# TEC_driver.net
KiCad netlist of a schematic drawn in Altium Designer
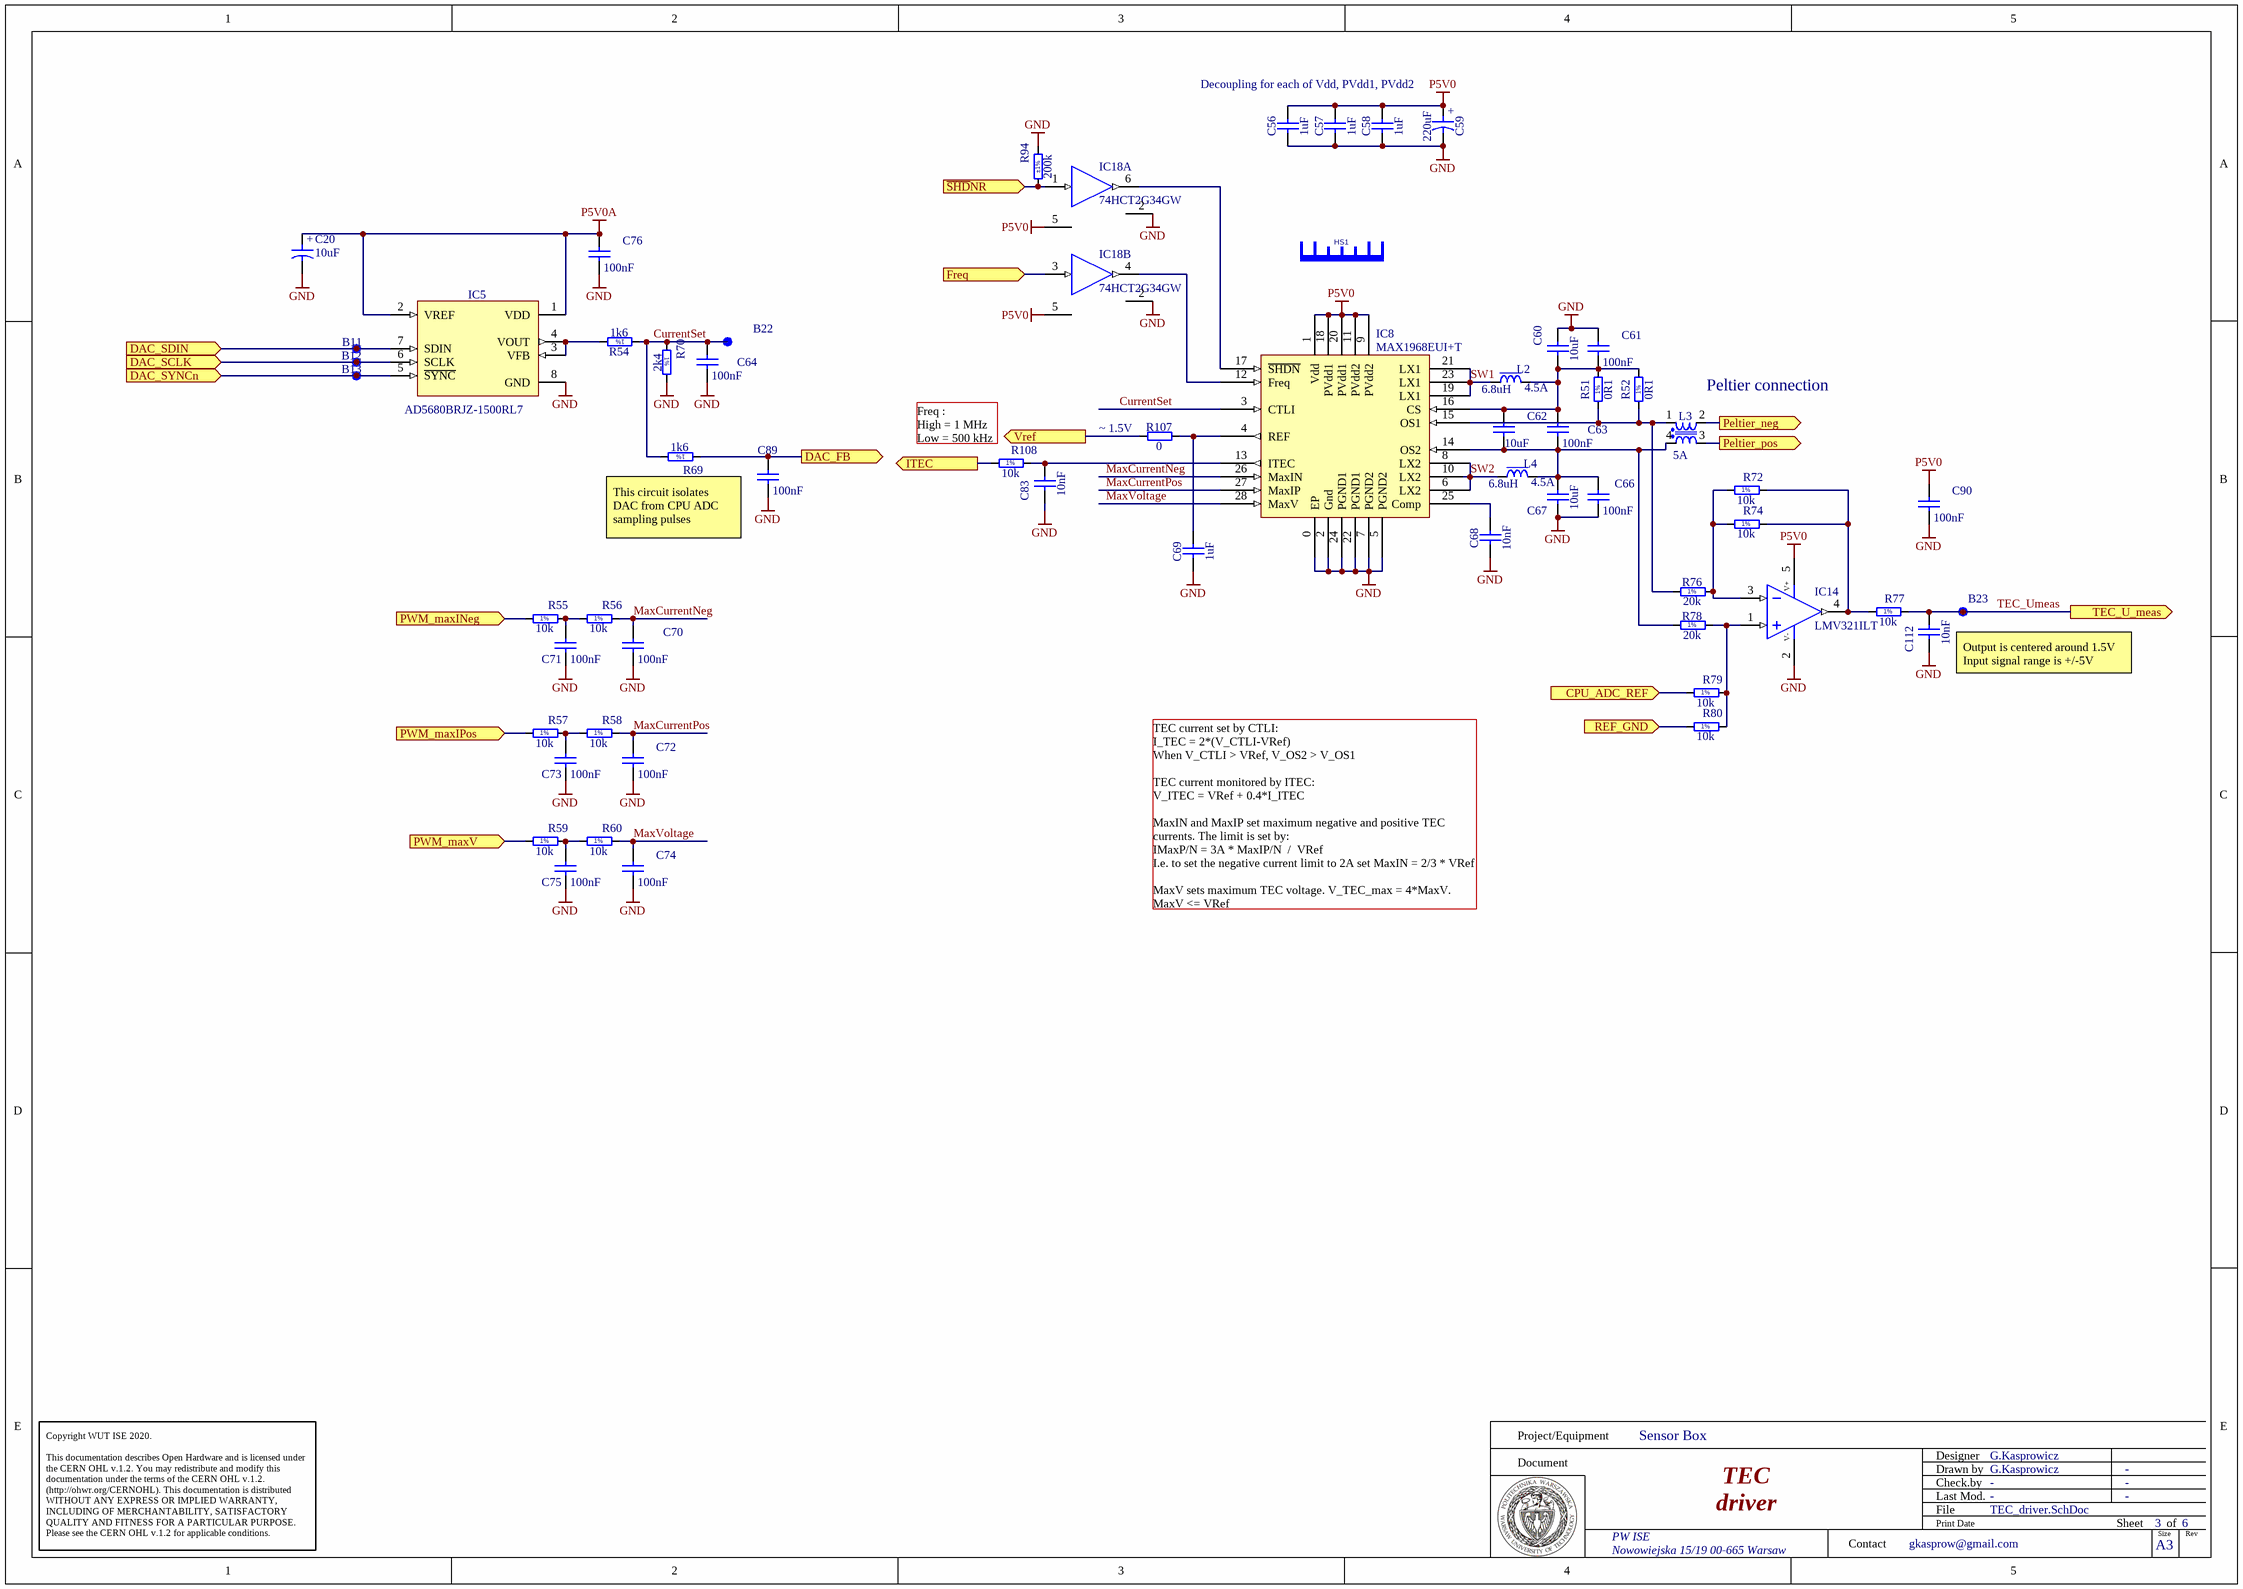
[diagram p0: TEC_driver.SchDoc]

(export (version "E")
  (design (tool "Eeschema 10.0.6"))
  (components
    (comp (ref "B11")
      (value "SMD Pad")
      (footprint "C100")
      (description "Through Hole Pad")
      (fields (field (name "PART NUMBER") "SMD_PAD_D1MM") (field (name "AUTHOR") "CERN DEM JLC"))
      (libsource (lib "Eletro-mechanical") (part "Single SMD Pad (Round)"))
    )
    (comp (ref "B12")
      (value "SMD Pad")
      (footprint "C100")
      (description "Through Hole Pad")
      (fields (field (name "PART NUMBER") "SMD_PAD_D1MM") (field (name "AUTHOR") "CERN DEM JLC"))
      (libsource (lib "Eletro-mechanical") (part "Single SMD Pad (Round)"))
    )
    (comp (ref "B13")
      (value "SMD Pad")
      (footprint "C100")
      (description "Through Hole Pad")
      (fields (field (name "PART NUMBER") "SMD_PAD_D1MM") (field (name "AUTHOR") "CERN DEM JLC"))
      (libsource (lib "Eletro-mechanical") (part "Single SMD Pad (Round)"))
    )
    (comp (ref "B22")
      (value "SMD Pad")
      (footprint "C100")
      (description "Through Hole Pad")
      (fields (field (name "PART NUMBER") "SMD_PAD_D1MM") (field (name "AUTHOR") "CERN DEM JLC"))
      (libsource (lib "Eletro-mechanical") (part "Single SMD Pad (Round)"))
    )
    (comp (ref "B23")
      (value "SMD Pad")
      (footprint "C100")
      (description "Through Hole Pad")
      (fields (field (name "PART NUMBER") "SMD_PAD_D1MM") (field (name "AUTHOR") "CERN DEM JLC"))
      (libsource (lib "Eletro-mechanical") (part "Single SMD Pad (Round)"))
    )
    (comp (ref "C20")
      (value "10uF")
      (footprint "CAPMP3216X180N")
      (description "Polarised capacitor")
      (fields
        (field (name "PART NUMBER") "CTE3216-18_10UF_16V_20%_AVX_TCJ")
        (field (name "VOLTAGE") "16V")
        (field (name "AUTHOR") "CERN DEM JLC")
      )
      (libsource (lib "Capacitors") (part "Capacitor - polarized"))
    )
    (comp (ref "C56")
      (value "1uF")
      (footprint "CAPC1608X87N")
      (description "Non-polarised capacitor")
      (fields
        (field (name "PART NUMBER") "CC0603_1UF_25V_10%_X7R")
        (field (name "VOLTAGE") "25V")
        (field (name "AUTHOR") "CERN DEM JLC")
      )
      (libsource (lib "Capacitors") (part "Capacitor - non polarized"))
    )
    (comp (ref "C57")
      (value "1uF")
      (footprint "CAPC1608X87N")
      (description "Non-polarised capacitor")
      (fields
        (field (name "PART NUMBER") "CC0603_1UF_25V_10%_X7R")
        (field (name "VOLTAGE") "25V")
        (field (name "AUTHOR") "CERN DEM JLC")
      )
      (libsource (lib "Capacitors") (part "Capacitor - non polarized"))
    )
    (comp (ref "C58")
      (value "1uF")
      (footprint "CAPC1608X87N")
      (description "Non-polarised capacitor")
      (fields
        (field (name "PART NUMBER") "CC0603_1UF_25V_10%_X7R")
        (field (name "VOLTAGE") "25V")
        (field (name "AUTHOR") "CERN DEM JLC")
      )
      (libsource (lib "Capacitors") (part "Capacitor - non polarized"))
    )
    (comp (ref "C59")
      (value "220uF")
      (footprint "CAPMP7343X430N")
      (description "Polarised capacitor")
      (fields
        (field (name "PART NUMBER") "CTE7343-43_220UF_16V_10%")
        (field (name "VOLTAGE") "16V")
        (field (name "AUTHOR") "CERN DEM JLC")
      )
      (libsource (lib "Capacitors") (part "Capacitor - polarized"))
    )
    (comp (ref "C60")
      (value "10uF")
      (footprint "CAPC2012X135N")
      (description "Non-polarised capacitor")
      (fields
        (field (name "PART NUMBER") "CC0805_10UF_16V_10%_X5R")
        (field (name "VOLTAGE") "16V")
        (field (name "AUTHOR") "CERN DEM JLC")
      )
      (libsource (lib "Capacitors") (part "Capacitor - non polarized"))
    )
    (comp (ref "C61")
      (value "100nF")
      (footprint "CAPC1005X55N")
      (description "Non-polarised capacitor")
      (fields
        (field (name "PART NUMBER") "CC0402_100NF_16V_10%_X5R")
        (field (name "VOLTAGE") "16V")
        (field (name "AUTHOR") "CERN DEM JLC")
      )
      (libsource (lib "Capacitors") (part "Capacitor - non polarized"))
    )
    (comp (ref "C62")
      (value "10uF")
      (footprint "CAPC2012X135N")
      (description "Non-polarised capacitor")
      (fields
        (field (name "PART NUMBER") "CC0805_10UF_16V_10%_X5R")
        (field (name "VOLTAGE") "16V")
        (field (name "AUTHOR") "CERN DEM JLC")
      )
      (libsource (lib "Capacitors") (part "Capacitor - non polarized"))
    )
    (comp (ref "C63")
      (value "100nF")
      (footprint "CAPC1005X55N")
      (description "Non-polarised capacitor")
      (fields
        (field (name "PART NUMBER") "CC0402_100NF_16V_10%_X5R")
        (field (name "VOLTAGE") "16V")
        (field (name "AUTHOR") "CERN DEM JLC")
      )
      (libsource (lib "Capacitors") (part "Capacitor - non polarized"))
    )
    (comp (ref "C64")
      (value "100nF")
      (footprint "CAPC1005X55N")
      (description "Non-polarised capacitor")
      (fields
        (field (name "PART NUMBER") "CC0402_100NF_16V_10%_X5R")
        (field (name "VOLTAGE") "16V")
        (field (name "AUTHOR") "CERN DEM JLC")
      )
      (libsource (lib "Capacitors") (part "Capacitor - non polarized"))
    )
    (comp (ref "C66")
      (value "100nF")
      (footprint "CAPC1005X55N")
      (description "Non-polarised capacitor")
      (fields
        (field (name "PART NUMBER") "CC0402_100NF_16V_10%_X5R")
        (field (name "VOLTAGE") "16V")
        (field (name "AUTHOR") "CERN DEM JLC")
      )
      (libsource (lib "Capacitors") (part "Capacitor - non polarized"))
    )
    (comp (ref "C67")
      (value "10uF")
      (footprint "CAPC2012X135N")
      (description "Non-polarised capacitor")
      (fields
        (field (name "PART NUMBER") "CC0805_10UF_16V_10%_X5R")
        (field (name "VOLTAGE") "16V")
        (field (name "AUTHOR") "CERN DEM JLC")
      )
      (libsource (lib "Capacitors") (part "Capacitor - non polarized"))
    )
    (comp (ref "C68")
      (value "10nF")
      (footprint "CAPC1005X55N")
      (description "Non-polarised capacitor")
      (fields
        (field (name "PART NUMBER") "CC0402_10NF_50V_10%_X7R")
        (field (name "VOLTAGE") "50V")
        (field (name "AUTHOR") "CERN DEM MR")
      )
      (libsource (lib "Capacitors") (part "Capacitor - non polarized"))
    )
    (comp (ref "C69")
      (value "1uF")
      (footprint "CAPC1608X87N")
      (description "Non-polarised capacitor")
      (fields
        (field (name "PART NUMBER") "CC0603_1UF_25V_10%_X7R")
        (field (name "VOLTAGE") "25V")
        (field (name "AUTHOR") "CERN DEM JLC")
      )
      (libsource (lib "Capacitors") (part "Capacitor - non polarized"))
    )
    (comp (ref "C70")
      (value "100nF")
      (footprint "CAPC1005X55N")
      (description "Non-polarised capacitor")
      (fields
        (field (name "PART NUMBER") "CC0402_100NF_16V_10%_X5R")
        (field (name "VOLTAGE") "16V")
        (field (name "AUTHOR") "CERN DEM JLC")
      )
      (libsource (lib "Capacitors") (part "Capacitor - non polarized"))
    )
    (comp (ref "C71")
      (value "100nF")
      (footprint "CAPC1005X55N")
      (description "Non-polarised capacitor")
      (fields
        (field (name "PART NUMBER") "CC0402_100NF_16V_10%_X5R")
        (field (name "VOLTAGE") "16V")
        (field (name "AUTHOR") "CERN DEM JLC")
      )
      (libsource (lib "Capacitors") (part "Capacitor - non polarized"))
    )
    (comp (ref "C72")
      (value "100nF")
      (footprint "CAPC1005X55N")
      (description "Non-polarised capacitor")
      (fields
        (field (name "PART NUMBER") "CC0402_100NF_16V_10%_X5R")
        (field (name "VOLTAGE") "16V")
        (field (name "AUTHOR") "CERN DEM JLC")
      )
      (libsource (lib "Capacitors") (part "Capacitor - non polarized"))
    )
    (comp (ref "C73")
      (value "100nF")
      (footprint "CAPC1005X55N")
      (description "Non-polarised capacitor")
      (fields
        (field (name "PART NUMBER") "CC0402_100NF_16V_10%_X5R")
        (field (name "VOLTAGE") "16V")
        (field (name "AUTHOR") "CERN DEM JLC")
      )
      (libsource (lib "Capacitors") (part "Capacitor - non polarized"))
    )
    (comp (ref "C74")
      (value "100nF")
      (footprint "CAPC1005X55N")
      (description "Non-polarised capacitor")
      (fields
        (field (name "PART NUMBER") "CC0402_100NF_16V_10%_X5R")
        (field (name "VOLTAGE") "16V")
        (field (name "AUTHOR") "CERN DEM JLC")
      )
      (libsource (lib "Capacitors") (part "Capacitor - non polarized"))
    )
    (comp (ref "C75")
      (value "100nF")
      (footprint "CAPC1005X55N")
      (description "Non-polarised capacitor")
      (fields
        (field (name "PART NUMBER") "CC0402_100NF_16V_10%_X5R")
        (field (name "VOLTAGE") "16V")
        (field (name "AUTHOR") "CERN DEM JLC")
      )
      (libsource (lib "Capacitors") (part "Capacitor - non polarized"))
    )
    (comp (ref "C76")
      (value "100nF")
      (footprint "CAPC1005X55N")
      (description "Non-polarised capacitor")
      (fields
        (field (name "PART NUMBER") "CC0402_100NF_16V_10%_X5R")
        (field (name "VOLTAGE") "16V")
        (field (name "AUTHOR") "CERN DEM JLC")
      )
      (libsource (lib "Capacitors") (part "Capacitor - non polarized"))
    )
    (comp (ref "C83")
      (value "10nF")
      (footprint "CAPC1005X55N")
      (description "Non-polarised capacitor")
      (fields
        (field (name "PART NUMBER") "CC0402_10NF_25V_10%_X7R")
        (field (name "VOLTAGE") "25V")
        (field (name "AUTHOR") "CERN DEM JLC")
      )
      (libsource (lib "Capacitors") (part "Capacitor - non polarized"))
    )
    (comp (ref "C89")
      (value "100nF")
      (footprint "CAPC1005X55N")
      (description "Non-polarised capacitor")
      (fields
        (field (name "PART NUMBER") "CC0402_100NF_16V_10%_X5R")
        (field (name "VOLTAGE") "16V")
        (field (name "AUTHOR") "CERN DEM JLC")
      )
      (libsource (lib "Capacitors") (part "Capacitor - non polarized"))
    )
    (comp (ref "C90")
      (value "100nF")
      (footprint "CAPC1005X55N")
      (description "Non-polarised capacitor")
      (fields
        (field (name "PART NUMBER") "CC0402_100NF_16V_10%_X5R")
        (field (name "VOLTAGE") "16V")
        (field (name "AUTHOR") "CERN DEM JLC")
      )
      (libsource (lib "Capacitors") (part "Capacitor - non polarized"))
    )
    (comp (ref "C112")
      (value "10nF")
      (footprint "CAPC1005X55N")
      (description "Non-polarised capacitor")
      (fields
        (field (name "PART NUMBER") "CC0402_10NF_25V_10%_X7R")
        (field (name "VOLTAGE") "25V")
        (field (name "AUTHOR") "CERN DEM JLC")
      )
      (libsource (lib "Capacitors") (part "Capacitor - non polarized"))
    )
    (comp (ref "HS1")
      (value "Heat Sink No Pad")
      (footprint "HSINK_FISCHER_ICK_BGA_11x11x10")
      (description "Rth: 27.5K/W - L 11mm x W 11mm x H 10mm Black Anodized Heatsinks for BGA")
      (fields
        (field (name "PART NUMBER") "HSINK_FISCHER_ICK BGA 11 x 11 x 10")
        (field (name "MANUFACTURER") "FISCHER ELEKTRONIK")
        (field (name "AUTHOR") "GK")
      )
      (libsource (lib "Mechanical") (part "HEAT_SINK_BGA_11x11x10"))
    )
    (comp (ref "IC5")
      (value "AD5680BRJZ-1500RL7")
      (footprint "SOT65P280X145-8N")
      (description "5V 18-Bit nanoDAC®in a SOT-23")
      (fields (field (name "MANUFACTURER") "ANALOG DEVICES") (field (name "AUTHOR") "GK"))
      (libsource (lib "LIBRARY_SCH") (part "DAC_AD5680BRJZ"))
    )
    (comp (ref "IC8")
      (value "MAX1968EUI+T")
      (footprint "TSSOP28-EP")
      (description "Power peltier driver. bipolar")
      (fields (field (name "PUBLISHER") "Altium Limited"))
      (libsource (lib "LIBRARY_SCH") (part "DRV_MAX1968"))
    )
    (comp (ref "IC14")
      (value "LMV321ILT")
      (footprint "SOT95P280X145-5N")
      (description "Operational Amplifier")
      (fields (field (name "MANUFACTURER") "ST MICROELECTRONICS") (field (name "AUTHOR") "CERN DEM MR"))
      (libsource (lib "ICs And Semiconductors") (part "Operational Amplifier Type10"))
    )
    (comp (ref "IC18")
      (value "74HCT2G34GW")
      (footprint "SOT65P210X110-6N")
      (description "Dual Buffer Gate")
      (fields (field (name "MANUFACTURER") "TEXAS INSTRUMENTS") (field (name "AUTHOR") "GK"))
      (libsource (lib "ICS-logic") (part "74HCT2G34GW"))
    )
    (comp (ref "L2")
      (value "6.8uH")
      (footprint "INDM6965X300N")
      (description "Inductor With Core")
      (fields
        (field (name "PART NUMBER") "IND2525_6.8UH_20%_VISHAY_IHLP-2525CZ-01")
        (field (name "POWER") "4.5A")
        (field (name "TOLERANCE") "±20%")
        (field (name "AUTHOR") "CERN DEM MR")
      )
      (libsource (lib "Inductors & Transformers") (part "Inductor With Magnetic core"))
    )
    (comp (ref "L3")
      (value "600nH")
      (footprint "IND_BOURNS_SRF0504-191Y")
      (description "Inductor Common Mode")
      (fields
        (field (name "PART NUMBER") "IND_600NH_30%_BOURNS_SRF0504")
        (field (name "POWER") "5A")
        (field (name "TOLERANCE") "±30%")
        (field (name "AUTHOR") "CERN DEM MR")
      )
      (libsource (lib "Inductors & Transformers") (part "Inductor Common Mode 1Dot-2 4Dot-3"))
    )
    (comp (ref "L4")
      (value "6.8uH")
      (footprint "INDM6965X300N")
      (description "Inductor With Core")
      (fields
        (field (name "PART NUMBER") "IND2525_6.8UH_20%_VISHAY_IHLP-2525CZ-01")
        (field (name "POWER") "4.5A")
        (field (name "TOLERANCE") "±20%")
        (field (name "AUTHOR") "CERN DEM MR")
      )
      (libsource (lib "Inductors & Transformers") (part "Inductor With Magnetic core"))
    )
    (comp (ref "R51")
      (value "0R1")
      (footprint "RESC3216X65N")
      (description "Resistor - 1%")
      (fields
        (field (name "PART NUMBER") "R1206_0R1_1%_0.25W_100PPM_YAGEO_PT")
        (field (name "POWER") "0.25W")
        (field (name "AUTHOR") "CERN DEM JMW")
      )
      (libsource (lib "Resistors") (part "Resistor - 1%"))
    )
    (comp (ref "R52")
      (value "0R1")
      (footprint "RESC3216X65N")
      (description "Resistor - 1%")
      (fields
        (field (name "PART NUMBER") "R1206_0R1_1%_0.25W_100PPM_YAGEO_PT")
        (field (name "POWER") "0.25W")
        (field (name "AUTHOR") "CERN DEM JMW")
      )
      (libsource (lib "Resistors") (part "Resistor - 1%"))
    )
    (comp (ref "R54")
      (value "1k6")
      (footprint "RESC1005X40N")
      (description "Resistor - 1%")
      (fields
        (field (name "PART NUMBER") "R0402_1K6_1%_0.0625W_100PPM")
        (field (name "POWER") "0.0625W")
        (field (name "AUTHOR") "CERN DEM JLC")
      )
      (libsource (lib "Resistors") (part "Resistor - 1%"))
    )
    (comp (ref "R55")
      (value "10k")
      (footprint "RESC1005X40N")
      (description "Resistor - 1%")
      (fields
        (field (name "PART NUMBER") "R0402_10K_1%_0.0625W_100PPM")
        (field (name "POWER") "0.0625W")
        (field (name "AUTHOR") "CERN DEM JLC")
      )
      (libsource (lib "Resistors") (part "Resistor - 1%"))
    )
    (comp (ref "R56")
      (value "10k")
      (footprint "RESC1005X40N")
      (description "Resistor - 1%")
      (fields
        (field (name "PART NUMBER") "R0402_10K_1%_0.0625W_100PPM")
        (field (name "POWER") "0.0625W")
        (field (name "AUTHOR") "CERN DEM JLC")
      )
      (libsource (lib "Resistors") (part "Resistor - 1%"))
    )
    (comp (ref "R57")
      (value "10k")
      (footprint "RESC1005X40N")
      (description "Resistor - 1%")
      (fields
        (field (name "PART NUMBER") "R0402_10K_1%_0.0625W_100PPM")
        (field (name "POWER") "0.0625W")
        (field (name "AUTHOR") "CERN DEM JLC")
      )
      (libsource (lib "Resistors") (part "Resistor - 1%"))
    )
    (comp (ref "R58")
      (value "10k")
      (footprint "RESC1005X40N")
      (description "Resistor - 1%")
      (fields
        (field (name "PART NUMBER") "R0402_10K_1%_0.0625W_100PPM")
        (field (name "POWER") "0.0625W")
        (field (name "AUTHOR") "CERN DEM JLC")
      )
      (libsource (lib "Resistors") (part "Resistor - 1%"))
    )
    (comp (ref "R59")
      (value "10k")
      (footprint "RESC1005X40N")
      (description "Resistor - 1%")
      (fields
        (field (name "PART NUMBER") "R0402_10K_1%_0.0625W_100PPM")
        (field (name "POWER") "0.0625W")
        (field (name "AUTHOR") "CERN DEM JLC")
      )
      (libsource (lib "Resistors") (part "Resistor - 1%"))
    )
    (comp (ref "R60")
      (value "10k")
      (footprint "RESC1005X40N")
      (description "Resistor - 1%")
      (fields
        (field (name "PART NUMBER") "R0402_10K_1%_0.0625W_100PPM")
        (field (name "POWER") "0.0625W")
        (field (name "AUTHOR") "CERN DEM JLC")
      )
      (libsource (lib "Resistors") (part "Resistor - 1%"))
    )
    (comp (ref "R69")
      (value "1k6")
      (footprint "RESC1005X40N")
      (description "Resistor - 1%")
      (fields
        (field (name "PART NUMBER") "R0402_1K6_1%_0.0625W_100PPM")
        (field (name "POWER") "0.0625W")
        (field (name "AUTHOR") "CERN DEM JLC")
      )
      (libsource (lib "Resistors") (part "Resistor - 1%"))
    )
    (comp (ref "R70")
      (value "2k4")
      (footprint "RESC1005X40N")
      (description "Resistor - 1%")
      (fields
        (field (name "PART NUMBER") "R0402_2K4_1%_0.0625W_100PPM")
        (field (name "POWER") "0.0625W")
        (field (name "AUTHOR") "CERN DEM JLC")
      )
      (libsource (lib "Resistors") (part "Resistor - 1%"))
    )
    (comp (ref "R72")
      (value "10k")
      (footprint "RESC1005X40N")
      (description "Resistor - 1%")
      (fields
        (field (name "PART NUMBER") "R0402_10K_1%_0.0625W_100PPM")
        (field (name "POWER") "0.0625W")
        (field (name "AUTHOR") "CERN DEM JLC")
      )
      (libsource (lib "Resistors") (part "Resistor - 1%"))
    )
    (comp (ref "R74")
      (value "10k")
      (footprint "RESC1005X40N")
      (description "Resistor - 1%")
      (fields
        (field (name "PART NUMBER") "R0402_10K_1%_0.0625W_100PPM")
        (field (name "POWER") "0.0625W")
        (field (name "AUTHOR") "CERN DEM JLC")
      )
      (libsource (lib "Resistors") (part "Resistor - 1%"))
    )
    (comp (ref "R76")
      (value "20k")
      (footprint "RESC1005X40N")
      (description "Resistor - 1%")
      (fields
        (field (name "PART NUMBER") "R0402_20K_1%_0.0625W_100PPM")
        (field (name "POWER") "0.0625W")
        (field (name "AUTHOR") "CERN DEM JLC")
      )
      (libsource (lib "Resistors") (part "Resistor - 1%"))
    )
    (comp (ref "R77")
      (value "10k")
      (footprint "RESC1005X40N")
      (description "Resistor - 1%")
      (fields
        (field (name "PART NUMBER") "R0402_10K_1%_0.0625W_100PPM")
        (field (name "POWER") "0.0625W")
        (field (name "AUTHOR") "CERN DEM JLC")
      )
      (libsource (lib "Resistors") (part "Resistor - 1%"))
    )
    (comp (ref "R78")
      (value "20k")
      (footprint "RESC1005X40N")
      (description "Resistor - 1%")
      (fields
        (field (name "PART NUMBER") "R0402_20K_1%_0.0625W_100PPM")
        (field (name "POWER") "0.0625W")
        (field (name "AUTHOR") "CERN DEM JLC")
      )
      (libsource (lib "Resistors") (part "Resistor - 1%"))
    )
    (comp (ref "R79")
      (value "10k")
      (footprint "RESC1005X40N")
      (description "Resistor - 1%")
      (fields
        (field (name "PART NUMBER") "R0402_10K_1%_0.0625W_100PPM")
        (field (name "POWER") "0.0625W")
        (field (name "AUTHOR") "CERN DEM JLC")
      )
      (libsource (lib "Resistors") (part "Resistor - 1%"))
    )
    (comp (ref "R80")
      (value "10k")
      (footprint "RESC1005X40N")
      (description "Resistor - 1%")
      (fields
        (field (name "PART NUMBER") "R0402_10K_1%_0.0625W_100PPM")
        (field (name "POWER") "0.0625W")
        (field (name "AUTHOR") "CERN DEM JLC")
      )
      (libsource (lib "Resistors") (part "Resistor - 1%"))
    )
    (comp (ref "R94")
      (value "200k")
      (footprint "RESC1005X40N")
      (description "Resistor - 1%")
      (fields
        (field (name "TOLERANCE") "±1%")
        (field (name "PART NUMBER") "R0402_200K_1%_0.0625W_100PPM")
        (field (name "POWER") "0.0625W")
        (field (name "AUTHOR") "CERN DEM JLC")
      )
      (libsource (lib "Resistors") (part "Resistor - 1%"))
    )
    (comp (ref "R107")
      (value "0")
      (footprint "RESC1005X40N")
      (description "Resistor")
      (fields
        (field (name "PART NUMBER") "R0402_0R_JUMPER")
        (field (name "MANUFACTURER") "GENERIC")
        (field (name "AUTHOR") "CERN DEM JLC")
      )
      (libsource (lib "Resistors") (part "Resistor"))
    )
    (comp (ref "R108")
      (value "10k")
      (footprint "RESC1005X40N")
      (description "Resistor - 1%")
      (fields
        (field (name "PART NUMBER") "R0402_10K_1%_0.0625W_100PPM")
        (field (name "POWER") "0.0625W")
        (field (name "AUTHOR") "CERN DEM JLC")
      )
      (libsource (lib "Resistors") (part "Resistor - 1%"))
    )
  )
  (nets
    (net (code "1") (name "/CPU_ADC_REF") (class "Default")
      (node (ref "R79") (pin "1") (pinfunction "1_1") (pintype "passive"))
    )
    (net (code "2") (name "/CurrentSet") (class "Default")
      (node (ref "B22") (pin "1") (pinfunction "1_1") (pintype "bidirectional"))
      (node (ref "C64") (pin "1") (pinfunction "1_1") (pintype "passive"))
      (node (ref "IC8") (pin "3") (pinfunction "CTLI_3") (pintype "input"))
      (node (ref "R54") (pin "1") (pinfunction "1_1") (pintype "passive"))
      (node (ref "R69") (pin "2") (pinfunction "2_2") (pintype "passive"))
      (node (ref "R70") (pin "1") (pinfunction "1_1") (pintype "passive"))
    )
    (net (code "3") (name "/DAC_FB") (class "Default")
      (node (ref "C89") (pin "1") (pinfunction "1_1") (pintype "passive"))
      (node (ref "R69") (pin "1") (pinfunction "1_1") (pintype "passive"))
    )
    (net (code "4") (name "/DAC_SCLK") (class "Default")
      (node (ref "B12") (pin "1") (pinfunction "1_1") (pintype "bidirectional"))
      (node (ref "IC5") (pin "6") (pinfunction "SCLK_6") (pintype "input"))
    )
    (net (code "5") (name "/DAC_SDIN") (class "Default")
      (node (ref "B11") (pin "1") (pinfunction "1_1") (pintype "bidirectional"))
      (node (ref "IC5") (pin "7") (pinfunction "SDIN_7") (pintype "input"))
    )
    (net (code "6") (name "/DAC_SYNCn") (class "Default")
      (node (ref "B13") (pin "1") (pinfunction "1_1") (pintype "bidirectional"))
      (node (ref "IC5") (pin "5") (pinfunction "~{SYNC}_5") (pintype "input"))
    )
    (net (code "7") (name "/Freq") (class "Default")
      (node (ref "IC18") (pin "3") (pinfunction "2A_3") (pintype "input"))
    )
    (net (code "8") (name "/ITEC") (class "Default")
      (node (ref "R108") (pin "1") (pinfunction "1_1") (pintype "passive"))
    )
    (net (code "9") (name "/MaxCurrentNeg") (class "Default")
      (node (ref "C70") (pin "1") (pinfunction "1_1") (pintype "passive"))
      (node (ref "IC8") (pin "26") (pinfunction "MaxIN_26") (pintype "input"))
      (node (ref "R56") (pin "2") (pinfunction "2_2") (pintype "passive"))
    )
    (net (code "10") (name "/MaxCurrentPos") (class "Default")
      (node (ref "C72") (pin "1") (pinfunction "1_1") (pintype "passive"))
      (node (ref "IC8") (pin "27") (pinfunction "MaxIP_27") (pintype "input"))
      (node (ref "R58") (pin "2") (pinfunction "2_2") (pintype "passive"))
    )
    (net (code "11") (name "/MaxVoltage") (class "Default")
      (node (ref "C74") (pin "1") (pinfunction "1_1") (pintype "passive"))
      (node (ref "IC8") (pin "28") (pinfunction "MaxV_28") (pintype "input"))
      (node (ref "R60") (pin "2") (pinfunction "2_2") (pintype "passive"))
    )
    (net (code "12") (name "/PWM_maxINeg") (class "Default")
      (node (ref "R55") (pin "1") (pinfunction "1_1") (pintype "passive"))
    )
    (net (code "13") (name "/PWM_maxIPos") (class "Default")
      (node (ref "R57") (pin "1") (pinfunction "1_1") (pintype "passive"))
    )
    (net (code "14") (name "/PWM_maxV") (class "Default")
      (node (ref "R59") (pin "1") (pinfunction "1_1") (pintype "passive"))
    )
    (net (code "15") (name "/Peltier_neg") (class "Default")
      (node (ref "L3") (pin "2") (pinfunction "2_2") (pintype "passive"))
    )
    (net (code "16") (name "/Peltier_pos") (class "Default")
      (node (ref "L3") (pin "3") (pinfunction "3_3") (pintype "passive"))
    )
    (net (code "17") (name "/REF_GND") (class "Default")
      (node (ref "R80") (pin "1") (pinfunction "1_1") (pintype "passive"))
    )
    (net (code "18") (name "/SW1") (class "Default")
      (node (ref "IC8") (pin "19") (pinfunction "LX1_19") (pintype "power_in"))
      (node (ref "IC8") (pin "21") (pinfunction "LX1_21") (pintype "power_in"))
      (node (ref "IC8") (pin "23") (pinfunction "LX1_23") (pintype "power_in"))
      (node (ref "L2") (pin "1") (pinfunction "1_1") (pintype "passive"))
    )
    (net (code "19") (name "/SW2") (class "Default")
      (node (ref "IC8") (pin "10") (pinfunction "LX2_10") (pintype "power_in"))
      (node (ref "IC8") (pin "6") (pinfunction "LX2_6") (pintype "power_in"))
      (node (ref "IC8") (pin "8") (pinfunction "LX2_8") (pintype "power_in"))
      (node (ref "L4") (pin "1") (pinfunction "1_1") (pintype "passive"))
    )
    (net (code "20") (name "/TEC_Umeas") (class "Default")
      (node (ref "B23") (pin "1") (pinfunction "1_1") (pintype "bidirectional"))
      (node (ref "C112") (pin "2") (pinfunction "2_2") (pintype "passive"))
      (node (ref "R77") (pin "2") (pinfunction "2_2") (pintype "passive"))
    )
    (net (code "21") (name "/Vref") (class "Default")
      (node (ref "R107") (pin "1") (pinfunction "1_1") (pintype "passive"))
    )
    (net (code "22") (name "/~{SHD}NR") (class "Default")
      (node (ref "IC18") (pin "1") (pinfunction "1A_1") (pintype "input"))
      (node (ref "R94") (pin "1") (pinfunction "1_1") (pintype "passive"))
    )
    (net (code "23") (name "GND") (class "Default")
      (node (ref "C112") (pin "1") (pinfunction "1_1") (pintype "passive"))
      (node (ref "C20") (pin "2") (pinfunction "2_2") (pintype "passive"))
      (node (ref "C56") (pin "1") (pinfunction "1_1") (pintype "passive"))
      (node (ref "C57") (pin "1") (pinfunction "1_1") (pintype "passive"))
      (node (ref "C58") (pin "1") (pinfunction "1_1") (pintype "passive"))
      (node (ref "C59") (pin "2") (pinfunction "2_2") (pintype "passive"))
      (node (ref "C60") (pin "2") (pinfunction "2_2") (pintype "passive"))
      (node (ref "C61") (pin "1") (pinfunction "1_1") (pintype "passive"))
      (node (ref "C64") (pin "2") (pinfunction "2_2") (pintype "passive"))
      (node (ref "C66") (pin "2") (pinfunction "2_2") (pintype "passive"))
      (node (ref "C67") (pin "1") (pinfunction "1_1") (pintype "passive"))
      (node (ref "C68") (pin "1") (pinfunction "1_1") (pintype "passive"))
      (node (ref "C69") (pin "1") (pinfunction "1_1") (pintype "passive"))
      (node (ref "C70") (pin "2") (pinfunction "2_2") (pintype "passive"))
      (node (ref "C71") (pin "2") (pinfunction "2_2") (pintype "passive"))
      (node (ref "C72") (pin "2") (pinfunction "2_2") (pintype "passive"))
      (node (ref "C73") (pin "2") (pinfunction "2_2") (pintype "passive"))
      (node (ref "C74") (pin "2") (pinfunction "2_2") (pintype "passive"))
      (node (ref "C75") (pin "2") (pinfunction "2_2") (pintype "passive"))
      (node (ref "C76") (pin "2") (pinfunction "2_2") (pintype "passive"))
      (node (ref "C83") (pin "1") (pinfunction "1_1") (pintype "passive"))
      (node (ref "C89") (pin "2") (pinfunction "2_2") (pintype "passive"))
      (node (ref "C90") (pin "2") (pinfunction "2_2") (pintype "passive"))
      (node (ref "IC14") (pin "2") (pinfunction "V-_2") (pintype "power_in"))
      (node (ref "IC18") (pin "2") (pinfunction "GND_2") (pintype "power_in"))
      (node (ref "IC5") (pin "8") (pinfunction "GND_8") (pintype "power_in"))
      (node (ref "IC8") (pin "0") (pinfunction "EP_0") (pintype "passive"))
      (node (ref "IC8") (pin "2") (pinfunction "Gnd_2") (pintype "power_in"))
      (node (ref "IC8") (pin "22") (pinfunction "PGND1_22") (pintype "power_in"))
      (node (ref "IC8") (pin "24") (pinfunction "PGND1_24") (pintype "power_in"))
      (node (ref "IC8") (pin "5") (pinfunction "PGND2_5") (pintype "power_in"))
      (node (ref "IC8") (pin "7") (pinfunction "PGND2_7") (pintype "power_in"))
      (node (ref "R70") (pin "2") (pinfunction "2_2") (pintype "passive"))
      (node (ref "R94") (pin "2") (pinfunction "2_2") (pintype "passive"))
    )
    (net (code "24") (name "Net-(C71-Pad1)") (class "Default")
      (node (ref "C71") (pin "1") (pinfunction "1_1") (pintype "passive"))
      (node (ref "R55") (pin "2") (pinfunction "2_2") (pintype "passive"))
      (node (ref "R56") (pin "1") (pinfunction "1_1") (pintype "passive"))
    )
    (net (code "25") (name "Net-(C73-Pad1)") (class "Default")
      (node (ref "C73") (pin "1") (pinfunction "1_1") (pintype "passive"))
      (node (ref "R57") (pin "2") (pinfunction "2_2") (pintype "passive"))
      (node (ref "R58") (pin "1") (pinfunction "1_1") (pintype "passive"))
    )
    (net (code "26") (name "Net-(C75-Pad1)") (class "Default")
      (node (ref "C75") (pin "1") (pinfunction "1_1") (pintype "passive"))
      (node (ref "R59") (pin "2") (pinfunction "2_2") (pintype "passive"))
      (node (ref "R60") (pin "1") (pinfunction "1_1") (pintype "passive"))
    )
    (net (code "27") (name "Net-(IC5-VFB)") (class "Default")
      (node (ref "IC5") (pin "3") (pinfunction "VFB_3") (pintype "input"))
      (node (ref "IC5") (pin "4") (pinfunction "VOUT_4") (pintype "output"))
      (node (ref "R54") (pin "2") (pinfunction "2_2") (pintype "passive"))
    )
    (net (code "28") (name "Net-(IC8-CS)") (class "Default")
      (node (ref "C60") (pin "1") (pinfunction "1_1") (pintype "passive"))
      (node (ref "C61") (pin "2") (pinfunction "2_2") (pintype "passive"))
      (node (ref "C62") (pin "2") (pinfunction "2_2") (pintype "passive"))
      (node (ref "C63") (pin "1") (pinfunction "1_1") (pintype "passive"))
      (node (ref "IC8") (pin "16") (pinfunction "CS_16") (pintype "input"))
      (node (ref "L2") (pin "2") (pinfunction "2_2") (pintype "passive"))
      (node (ref "R51") (pin "2") (pinfunction "2_2") (pintype "passive"))
      (node (ref "R52") (pin "2") (pinfunction "2_2") (pintype "passive"))
    )
    (net (code "29") (name "Net-(IC8-Comp)") (class "Default")
      (node (ref "C68") (pin "2") (pinfunction "2_2") (pintype "passive"))
      (node (ref "IC8") (pin "25") (pinfunction "Comp_25") (pintype "passive"))
    )
    (net (code "30") (name "Net-(IC8-ITEC)") (class "Default")
      (node (ref "C83") (pin "2") (pinfunction "2_2") (pintype "passive"))
      (node (ref "IC8") (pin "13") (pinfunction "ITEC_13") (pintype "output"))
      (node (ref "R108") (pin "2") (pinfunction "2_2") (pintype "passive"))
    )
    (net (code "31") (name "Net-(IC8-OS1)") (class "Default")
      (node (ref "IC8") (pin "15") (pinfunction "OS1_15") (pintype "input"))
      (node (ref "L3") (pin "1") (pinfunction "1_1") (pintype "passive"))
      (node (ref "R51") (pin "1") (pinfunction "1_1") (pintype "passive"))
      (node (ref "R52") (pin "1") (pinfunction "1_1") (pintype "passive"))
      (node (ref "R76") (pin "1") (pinfunction "1_1") (pintype "passive"))
    )
    (net (code "32") (name "Net-(IC8-OS2)") (class "Default")
      (node (ref "C62") (pin "1") (pinfunction "1_1") (pintype "passive"))
      (node (ref "C63") (pin "2") (pinfunction "2_2") (pintype "passive"))
      (node (ref "C66") (pin "1") (pinfunction "1_1") (pintype "passive"))
      (node (ref "C67") (pin "2") (pinfunction "2_2") (pintype "passive"))
      (node (ref "IC8") (pin "14") (pinfunction "OS2_14") (pintype "input"))
      (node (ref "L3") (pin "4") (pinfunction "4_4") (pintype "passive"))
      (node (ref "L4") (pin "2") (pinfunction "2_2") (pintype "passive"))
      (node (ref "R78") (pin "1") (pinfunction "1_1") (pintype "passive"))
    )
    (net (code "33") (name "Net-(IC8-REF)") (class "Default")
      (node (ref "C69") (pin "2") (pinfunction "2_2") (pintype "passive"))
      (node (ref "IC8") (pin "4") (pinfunction "REF_4") (pintype "output"))
      (node (ref "R107") (pin "2") (pinfunction "2_2") (pintype "passive"))
    )
    (net (code "34") (name "Net-(IC14-IN+)") (class "Default")
      (node (ref "IC14") (pin "1") (pinfunction "IN+_1") (pintype "input"))
      (node (ref "R78") (pin "2") (pinfunction "2_2") (pintype "passive"))
      (node (ref "R79") (pin "2") (pinfunction "2_2") (pintype "passive"))
      (node (ref "R80") (pin "2") (pinfunction "2_2") (pintype "passive"))
    )
    (net (code "35") (name "Net-(IC14-IN-)") (class "Default")
      (node (ref "IC14") (pin "3") (pinfunction "IN-_3") (pintype "input"))
      (node (ref "R72") (pin "1") (pinfunction "1_1") (pintype "passive"))
      (node (ref "R74") (pin "1") (pinfunction "1_1") (pintype "passive"))
      (node (ref "R76") (pin "2") (pinfunction "2_2") (pintype "passive"))
    )
    (net (code "36") (name "Net-(IC14-OUT)") (class "Default")
      (node (ref "IC14") (pin "4") (pinfunction "OUT_4") (pintype "output"))
      (node (ref "R72") (pin "2") (pinfunction "2_2") (pintype "passive"))
      (node (ref "R74") (pin "2") (pinfunction "2_2") (pintype "passive"))
      (node (ref "R77") (pin "1") (pinfunction "1_1") (pintype "passive"))
    )
    (net (code "37") (name "Net-(IC18A-1Y)") (class "Default")
      (node (ref "IC18") (pin "6") (pinfunction "1Y_6") (pintype "output"))
      (node (ref "IC8") (pin "17") (pinfunction "~{SHDN}_17") (pintype "input"))
    )
    (net (code "38") (name "Net-(IC18B-2Y)") (class "Default")
      (node (ref "IC18") (pin "4") (pinfunction "2Y_4") (pintype "output"))
      (node (ref "IC8") (pin "12") (pinfunction "Freq_12") (pintype "input"))
    )
    (net (code "39") (name "P5V0") (class "Default")
      (node (ref "C56") (pin "2") (pinfunction "2_2") (pintype "passive"))
      (node (ref "C57") (pin "2") (pinfunction "2_2") (pintype "passive"))
      (node (ref "C58") (pin "2") (pinfunction "2_2") (pintype "passive"))
      (node (ref "C59") (pin "1") (pinfunction "1_1") (pintype "passive"))
      (node (ref "C90") (pin "1") (pinfunction "1_1") (pintype "passive"))
      (node (ref "IC14") (pin "5") (pinfunction "V+_5") (pintype "power_in"))
      (node (ref "IC18") (pin "5") (pinfunction "VCC_5") (pintype "power_in"))
      (node (ref "IC8") (pin "1") (pinfunction "Vdd_1") (pintype "power_in"))
      (node (ref "IC8") (pin "11") (pinfunction "PVdd2_11") (pintype "power_in"))
      (node (ref "IC8") (pin "18") (pinfunction "PVdd1_18") (pintype "power_in"))
      (node (ref "IC8") (pin "20") (pinfunction "PVdd1_20") (pintype "power_in"))
      (node (ref "IC8") (pin "9") (pinfunction "PVdd2_9") (pintype "power_in"))
    )
    (net (code "40") (name "P5V0A") (class "Default")
      (node (ref "C20") (pin "1") (pinfunction "1_1") (pintype "passive"))
      (node (ref "C76") (pin "1") (pinfunction "1_1") (pintype "passive"))
      (node (ref "IC5") (pin "1") (pinfunction "VDD_1") (pintype "power_in"))
      (node (ref "IC5") (pin "2") (pinfunction "VREF_2") (pintype "input"))
    )
  )
)
